# Sheet2.net
KiCad netlist of a schematic drawn in Altium Designer
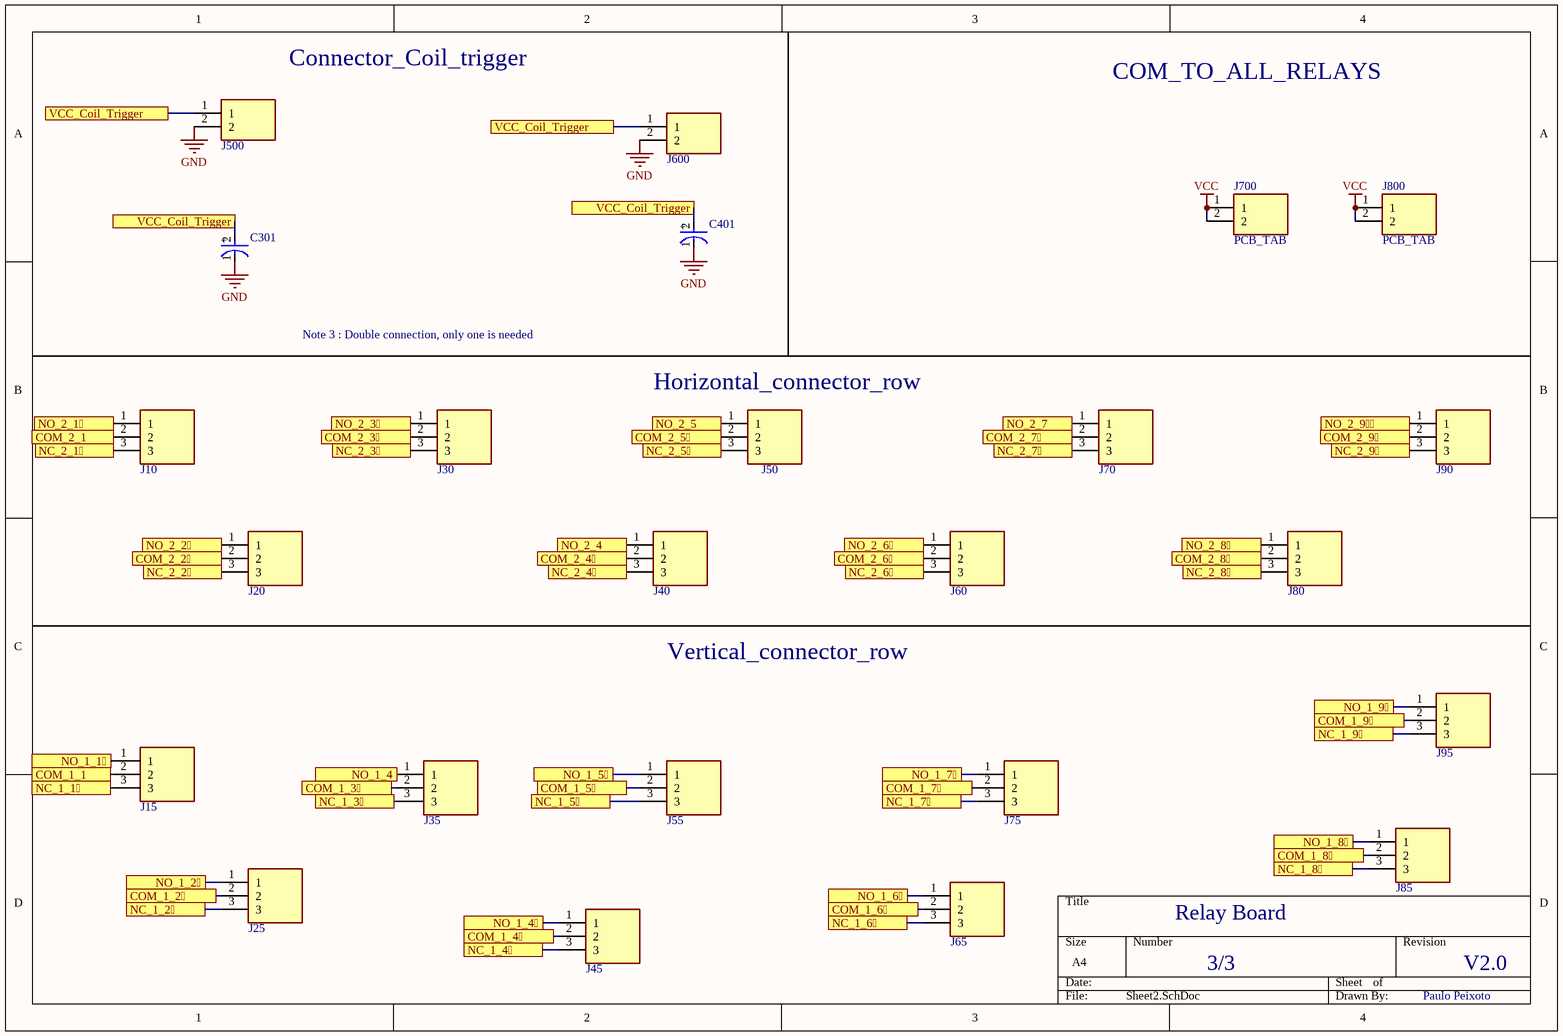
[diagram p0: Sheet2.SchDoc]

(export (version "E")
  (design (tool "Eeschema 10.0.6"))
  (components
    (comp (ref "C301")
      (value "EEE-FK1H100UR")
      (footprint "FP-FKC-MFG")
      (description "CAP ALUM 10UF 20% 50V SMD")
      (fields (field (name "TOLERANCE") "20%") (field (name "VOLTAGE") "50V"))
      (libsource (lib "Altium Content Vault") (part "a00bbbee19879c290e62620ae7e47b1"))
    )
    (comp (ref "C401")
      (value "EEE-FK1H100UR")
      (footprint "FP-FKC-MFG")
      (description "CAP ALUM 10UF 20% 50V SMD")
      (fields (field (name "TOLERANCE") "20%") (field (name "VOLTAGE") "50V"))
      (libsource (lib "Altium Content Vault") (part "a00bbbee19879c290e62620ae7e47b1"))
    )
    (comp (ref "J10")
      (value "1546551-3")
      (footprint "Terminal_3p_3.5mm_Horizontal")
      (description "Terminal")
      (fields (field (name "MOUSER PART NUMBER") "571-1546551-3"))
      (libsource (lib "GEPE_SchLib_Altium") (part "Con_Terminal_3P"))
    )
    (comp (ref "J15")
      (value "1546551-3")
      (footprint "Terminal_THT_3p_3.5mm_Vertical")
      (description "Terminal")
      (fields (field (name "MOUSER PART NUMBER") "571-1546551-3"))
      (libsource (lib "GEPE_SchLib_Altium") (part "Con_Terminal_3P"))
    )
    (comp (ref "J20")
      (value "1546551-3")
      (footprint "Terminal_3p_3.5mm_Horizontal")
      (description "Terminal")
      (fields (field (name "MOUSER PART NUMBER") "571-1546551-3"))
      (libsource (lib "GEPE_SchLib_Altium") (part "Con_Terminal_3P"))
    )
    (comp (ref "J25")
      (value "1546551-3")
      (footprint "Terminal_THT_3p_3.5mm_Vertical")
      (description "Terminal")
      (fields (field (name "MOUSER PART NUMBER") "571-1546551-3"))
      (libsource (lib "GEPE_SchLib_Altium") (part "Con_Terminal_3P"))
    )
    (comp (ref "J30")
      (value "1546551-3")
      (footprint "Terminal_3p_3.5mm_Horizontal")
      (description "Terminal")
      (fields (field (name "MOUSER PART NUMBER") "571-1546551-3"))
      (libsource (lib "GEPE_SchLib_Altium") (part "Con_Terminal_3P"))
    )
    (comp (ref "J35")
      (value "1546551-3")
      (footprint "Terminal_THT_3p_3.5mm_Vertical")
      (description "Terminal")
      (fields (field (name "MOUSER PART NUMBER") "571-1546551-3"))
      (libsource (lib "GEPE_SchLib_Altium") (part "Con_Terminal_3P"))
    )
    (comp (ref "J40")
      (value "1546551-3")
      (footprint "Terminal_3p_3.5mm_Horizontal")
      (description "Terminal")
      (fields (field (name "MOUSER PART NUMBER") "571-1546551-3"))
      (libsource (lib "GEPE_SchLib_Altium") (part "Con_Terminal_3P"))
    )
    (comp (ref "J45")
      (value "1546551-3")
      (footprint "Terminal_THT_3p_3.5mm_Vertical")
      (description "Terminal")
      (fields (field (name "MOUSER PART NUMBER") "571-1546551-3"))
      (libsource (lib "GEPE_SchLib_Altium") (part "Con_Terminal_3P"))
    )
    (comp (ref "J50")
      (value "1546551-3")
      (footprint "Terminal_3p_3.5mm_Horizontal")
      (description "Terminal")
      (fields (field (name "MOUSER PART NUMBER") "571-1546551-3"))
      (libsource (lib "GEPE_SchLib_Altium") (part "Con_Terminal_3P"))
    )
    (comp (ref "J55")
      (value "1546551-3")
      (footprint "Terminal_THT_3p_3.5mm_Vertical")
      (description "Terminal")
      (fields (field (name "MOUSER PART NUMBER") "571-1546551-3"))
      (libsource (lib "GEPE_SchLib_Altium") (part "Con_Terminal_3P"))
    )
    (comp (ref "J60")
      (value "1546551-3")
      (footprint "Terminal_3p_3.5mm_Horizontal")
      (description "Terminal")
      (fields (field (name "MOUSER PART NUMBER") "571-1546551-3"))
      (libsource (lib "GEPE_SchLib_Altium") (part "Con_Terminal_3P"))
    )
    (comp (ref "J65")
      (value "1546551-3")
      (footprint "Terminal_THT_3p_3.5mm_Vertical")
      (description "Terminal")
      (fields (field (name "MOUSER PART NUMBER") "571-1546551-3"))
      (libsource (lib "GEPE_SchLib_Altium") (part "Con_Terminal_3P"))
    )
    (comp (ref "J70")
      (value "1546551-3")
      (footprint "Terminal_3p_3.5mm_Horizontal")
      (description "Terminal")
      (fields (field (name "MOUSER PART NUMBER") "571-1546551-3"))
      (libsource (lib "GEPE_SchLib_Altium") (part "Con_Terminal_3P"))
    )
    (comp (ref "J75")
      (value "1546551-3")
      (footprint "Terminal_THT_3p_3.5mm_Vertical")
      (description "Terminal")
      (fields (field (name "MOUSER PART NUMBER") "571-1546551-3"))
      (libsource (lib "GEPE_SchLib_Altium") (part "Con_Terminal_3P"))
    )
    (comp (ref "J80")
      (value "1546551-3")
      (footprint "Terminal_3p_3.5mm_Horizontal")
      (description "Terminal")
      (fields (field (name "MOUSER PART NUMBER") "571-1546551-3"))
      (libsource (lib "GEPE_SchLib_Altium") (part "Con_Terminal_3P"))
    )
    (comp (ref "J85")
      (value "1546551-3")
      (footprint "Terminal_THT_3p_3.5mm_Vertical")
      (description "Terminal")
      (fields (field (name "MOUSER PART NUMBER") "571-1546551-3"))
      (libsource (lib "GEPE_SchLib_Altium") (part "Con_Terminal_3P"))
    )
    (comp (ref "J90")
      (value "1546551-3")
      (footprint "Terminal_3p_3.5mm_Horizontal")
      (description "Terminal")
      (fields (field (name "MOUSER PART NUMBER") "571-1546551-3"))
      (libsource (lib "GEPE_SchLib_Altium") (part "Con_Terminal_3P"))
    )
    (comp (ref "J95")
      (value "1546551-3")
      (footprint "Terminal_THT_3p_3.5mm_Vertical")
      (description "Terminal")
      (fields (field (name "MOUSER PART NUMBER") "571-1546551-3"))
      (libsource (lib "GEPE_SchLib_Altium") (part "Con_Terminal_3P"))
    )
    (comp (ref "J500")
      (value "TB004-508-02BE")
      (footprint "Terminal_TH_2P_3.50")
      (description "Connector")
      (fields (field (name "MOUSER PART NUMBER") "490-TB004-508-02BE"))
      (libsource (lib "GEPE_SchLib_Altium") (part "Con_Terminal_2P"))
    )
    (comp (ref "J600")
      (value "TB004-508-02BE")
      (footprint "Terminal_TH_2P_3.50")
      (description "Connector")
      (fields (field (name "MOUSER PART NUMBER") "490-TB004-508-02BE"))
      (libsource (lib "GEPE_SchLib_Altium") (part "Con_Terminal_2P"))
    )
    (comp (ref "J700")
      (value "PCB_TAB")
      (footprint "PCB_TAB_Vertical_6.35mm")
      (libsource (lib "GEPE_SchLib_Altium") (part "PCB_TAB"))
    )
    (comp (ref "J800")
      (value "PCB_TAB")
      (footprint "PCB_TAB_Vertical_6.35mm")
      (libsource (lib "GEPE_SchLib_Altium") (part "PCB_TAB"))
    )
  )
  (nets
    (net (code "1") (name "/COM_1_1") (class "Default")
      (node (ref "J15") (pin "2") (pinfunction "2_2") (pintype "passive"))
    )
    (net (code "2") (name "/COM_1_2") (class "Default")
      (node (ref "J25") (pin "2") (pinfunction "2_2") (pintype "passive"))
    )
    (net (code "3") (name "/COM_1_3") (class "Default")
      (node (ref "J35") (pin "2") (pinfunction "2_2") (pintype "passive"))
    )
    (net (code "4") (name "/COM_1_4") (class "Default")
      (node (ref "J45") (pin "2") (pinfunction "2_2") (pintype "passive"))
    )
    (net (code "5") (name "/COM_1_5") (class "Default")
      (node (ref "J55") (pin "2") (pinfunction "2_2") (pintype "passive"))
    )
    (net (code "6") (name "/COM_1_6") (class "Default")
      (node (ref "J65") (pin "2") (pinfunction "2_2") (pintype "passive"))
    )
    (net (code "7") (name "/COM_1_7") (class "Default")
      (node (ref "J75") (pin "2") (pinfunction "2_2") (pintype "passive"))
    )
    (net (code "8") (name "/COM_1_8") (class "Default")
      (node (ref "J85") (pin "2") (pinfunction "2_2") (pintype "passive"))
    )
    (net (code "9") (name "/COM_1_9") (class "Default")
      (node (ref "J95") (pin "2") (pinfunction "2_2") (pintype "passive"))
    )
    (net (code "10") (name "/COM_2_1") (class "Default")
      (node (ref "J10") (pin "2") (pinfunction "2_2") (pintype "passive"))
    )
    (net (code "11") (name "/COM_2_2") (class "Default")
      (node (ref "J20") (pin "2") (pinfunction "2_2") (pintype "passive"))
    )
    (net (code "12") (name "/COM_2_3") (class "Default")
      (node (ref "J30") (pin "2") (pinfunction "2_2") (pintype "passive"))
    )
    (net (code "13") (name "/COM_2_4") (class "Default")
      (node (ref "J40") (pin "2") (pinfunction "2_2") (pintype "passive"))
    )
    (net (code "14") (name "/COM_2_5") (class "Default")
      (node (ref "J50") (pin "2") (pinfunction "2_2") (pintype "passive"))
    )
    (net (code "15") (name "/COM_2_6") (class "Default")
      (node (ref "J60") (pin "2") (pinfunction "2_2") (pintype "passive"))
    )
    (net (code "16") (name "/COM_2_7") (class "Default")
      (node (ref "J70") (pin "2") (pinfunction "2_2") (pintype "passive"))
    )
    (net (code "17") (name "/COM_2_8") (class "Default")
      (node (ref "J80") (pin "2") (pinfunction "2_2") (pintype "passive"))
    )
    (net (code "18") (name "/COM_2_9") (class "Default")
      (node (ref "J90") (pin "2") (pinfunction "2_2") (pintype "passive"))
    )
    (net (code "19") (name "/NC_1_1") (class "Default")
      (node (ref "J15") (pin "3") (pinfunction "3_3") (pintype "passive"))
    )
    (net (code "20") (name "/NC_1_2") (class "Default")
      (node (ref "J25") (pin "3") (pinfunction "3_3") (pintype "passive"))
    )
    (net (code "21") (name "/NC_1_3") (class "Default")
      (node (ref "J35") (pin "3") (pinfunction "3_3") (pintype "passive"))
    )
    (net (code "22") (name "/NC_1_4") (class "Default")
      (node (ref "J45") (pin "3") (pinfunction "3_3") (pintype "passive"))
    )
    (net (code "23") (name "/NC_1_5") (class "Default")
      (node (ref "J55") (pin "3") (pinfunction "3_3") (pintype "passive"))
    )
    (net (code "24") (name "/NC_1_6") (class "Default")
      (node (ref "J65") (pin "3") (pinfunction "3_3") (pintype "passive"))
    )
    (net (code "25") (name "/NC_1_7") (class "Default")
      (node (ref "J75") (pin "3") (pinfunction "3_3") (pintype "passive"))
    )
    (net (code "26") (name "/NC_1_8") (class "Default")
      (node (ref "J85") (pin "3") (pinfunction "3_3") (pintype "passive"))
    )
    (net (code "27") (name "/NC_1_9") (class "Default")
      (node (ref "J95") (pin "3") (pinfunction "3_3") (pintype "passive"))
    )
    (net (code "28") (name "/NC_2_1") (class "Default")
      (node (ref "J10") (pin "3") (pinfunction "3_3") (pintype "passive"))
    )
    (net (code "29") (name "/NC_2_2") (class "Default")
      (node (ref "J20") (pin "3") (pinfunction "3_3") (pintype "passive"))
    )
    (net (code "30") (name "/NC_2_3") (class "Default")
      (node (ref "J30") (pin "3") (pinfunction "3_3") (pintype "passive"))
    )
    (net (code "31") (name "/NC_2_4") (class "Default")
      (node (ref "J40") (pin "3") (pinfunction "3_3") (pintype "passive"))
    )
    (net (code "32") (name "/NC_2_5") (class "Default")
      (node (ref "J50") (pin "3") (pinfunction "3_3") (pintype "passive"))
    )
    (net (code "33") (name "/NC_2_6") (class "Default")
      (node (ref "J60") (pin "3") (pinfunction "3_3") (pintype "passive"))
    )
    (net (code "34") (name "/NC_2_7") (class "Default")
      (node (ref "J70") (pin "3") (pinfunction "3_3") (pintype "passive"))
    )
    (net (code "35") (name "/NC_2_8") (class "Default")
      (node (ref "J80") (pin "3") (pinfunction "3_3") (pintype "passive"))
    )
    (net (code "36") (name "/NC_2_9") (class "Default")
      (node (ref "J90") (pin "3") (pinfunction "3_3") (pintype "passive"))
    )
    (net (code "37") (name "/NO_1_1") (class "Default")
      (node (ref "J15") (pin "1") (pinfunction "1_1") (pintype "passive"))
    )
    (net (code "38") (name "/NO_1_2") (class "Default")
      (node (ref "J25") (pin "1") (pinfunction "1_1") (pintype "passive"))
    )
    (net (code "39") (name "/NO_1_4") (class "Default")
      (node (ref "J35") (pin "1") (pinfunction "1_1") (pintype "passive"))
    )
    (net (code "40") (name "/NO_1_4") (class "Default")
      (node (ref "J45") (pin "1") (pinfunction "1_1") (pintype "passive"))
    )
    (net (code "41") (name "/NO_1_5") (class "Default")
      (node (ref "J55") (pin "1") (pinfunction "1_1") (pintype "passive"))
    )
    (net (code "42") (name "/NO_1_6") (class "Default")
      (node (ref "J65") (pin "1") (pinfunction "1_1") (pintype "passive"))
    )
    (net (code "43") (name "/NO_1_7") (class "Default")
      (node (ref "J75") (pin "1") (pinfunction "1_1") (pintype "passive"))
    )
    (net (code "44") (name "/NO_1_8") (class "Default")
      (node (ref "J85") (pin "1") (pinfunction "1_1") (pintype "passive"))
    )
    (net (code "45") (name "/NO_1_9") (class "Default")
      (node (ref "J95") (pin "1") (pinfunction "1_1") (pintype "passive"))
    )
    (net (code "46") (name "/NO_2_1") (class "Default")
      (node (ref "J10") (pin "1") (pinfunction "1_1") (pintype "passive"))
    )
    (net (code "47") (name "/NO_2_2") (class "Default")
      (node (ref "J20") (pin "1") (pinfunction "1_1") (pintype "passive"))
    )
    (net (code "48") (name "/NO_2_3") (class "Default")
      (node (ref "J30") (pin "1") (pinfunction "1_1") (pintype "passive"))
    )
    (net (code "49") (name "/NO_2_4") (class "Default")
      (node (ref "J40") (pin "1") (pinfunction "1_1") (pintype "passive"))
    )
    (net (code "50") (name "/NO_2_5") (class "Default")
      (node (ref "J50") (pin "1") (pinfunction "1_1") (pintype "passive"))
    )
    (net (code "51") (name "/NO_2_6") (class "Default")
      (node (ref "J60") (pin "1") (pinfunction "1_1") (pintype "passive"))
    )
    (net (code "52") (name "/NO_2_7") (class "Default")
      (node (ref "J70") (pin "1") (pinfunction "1_1") (pintype "passive"))
    )
    (net (code "53") (name "/NO_2_8") (class "Default")
      (node (ref "J80") (pin "1") (pinfunction "1_1") (pintype "passive"))
    )
    (net (code "54") (name "/NO_2_9") (class "Default")
      (node (ref "J90") (pin "1") (pinfunction "1_1") (pintype "passive"))
    )
    (net (code "55") (name "/VCC_Coil_Trigger") (class "Default")
      (node (ref "C301") (pin "2") (pinfunction "A_2") (pintype "passive"))
      (node (ref "C401") (pin "2") (pinfunction "A_2") (pintype "passive"))
      (node (ref "J500") (pin "1") (pinfunction "1_1") (pintype "passive"))
      (node (ref "J600") (pin "1") (pinfunction "1_1") (pintype "passive"))
    )
    (net (code "56") (name "GND") (class "Default")
      (node (ref "C301") (pin "1") (pinfunction "C_1") (pintype "passive"))
      (node (ref "C401") (pin "1") (pinfunction "C_1") (pintype "passive"))
      (node (ref "J500") (pin "2") (pinfunction "2_2") (pintype "passive"))
      (node (ref "J600") (pin "2") (pinfunction "2_2") (pintype "passive"))
    )
    (net (code "57") (name "VCC") (class "Default")
      (node (ref "J700") (pin "1") (pinfunction "1_1") (pintype "passive"))
      (node (ref "J700") (pin "2") (pinfunction "2_2") (pintype "passive"))
      (node (ref "J800") (pin "1") (pinfunction "1_1") (pintype "passive"))
      (node (ref "J800") (pin "2") (pinfunction "2_2") (pintype "passive"))
    )
  )
)
